# ver1_0.net
KiCad netlist of a schematic drawn in EAGLE
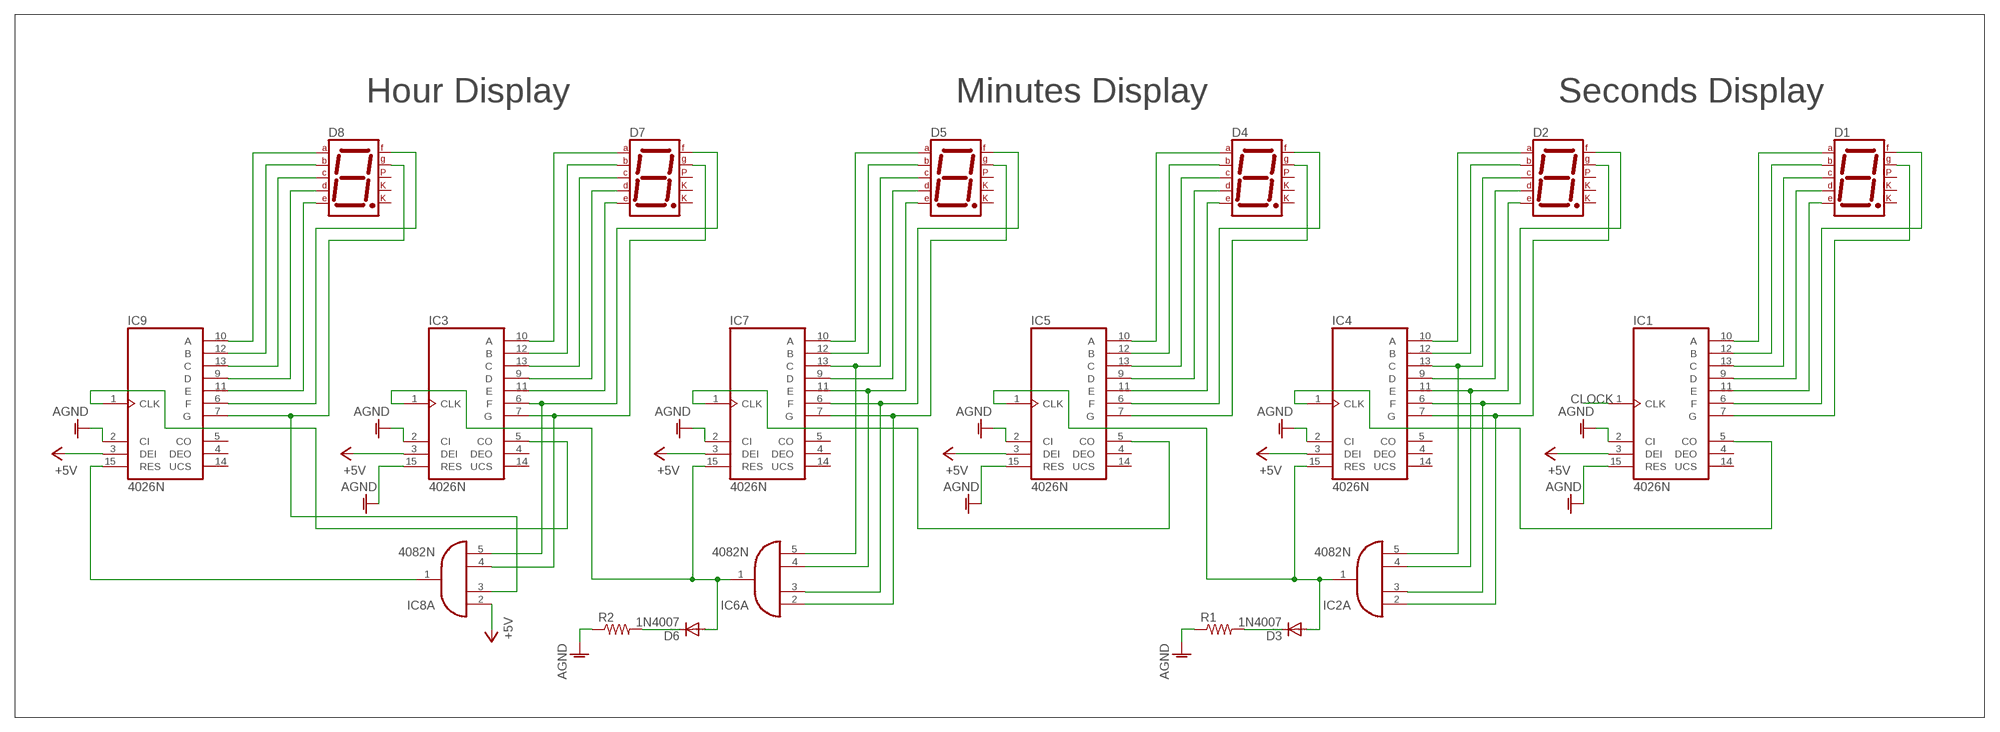
[diagram p0: schematic, sheet 1]

(export (version "E")
  (design (tool "Eeschema 10.0.6"))
  (components
    (comp (ref "D1")
      (value "7SEG-CK")
      (footprint "eagle-import:7SEG-13")
      (libsource (lib "eagle-import") (part "7SEG-CK"))
    )
    (comp (ref "D2")
      (value "7SEG-CK")
      (footprint "eagle-import:7SEG-13")
      (libsource (lib "eagle-import") (part "7SEG-CK"))
    )
    (comp (ref "D3")
      (value "1N4007")
      (footprint "eagle-import:DO41-10")
      (libsource (lib "eagle-import") (part "1N4004"))
    )
    (comp (ref "D4")
      (value "7SEG-CK")
      (footprint "eagle-import:7SEG-13")
      (libsource (lib "eagle-import") (part "7SEG-CK"))
    )
    (comp (ref "D5")
      (value "7SEG-CK")
      (footprint "eagle-import:7SEG-13")
      (libsource (lib "eagle-import") (part "7SEG-CK"))
    )
    (comp (ref "D6")
      (value "1N4007")
      (footprint "eagle-import:DO41-10")
      (libsource (lib "eagle-import") (part "1N4004"))
    )
    (comp (ref "D7")
      (value "7SEG-CK")
      (footprint "eagle-import:7SEG-13")
      (libsource (lib "eagle-import") (part "7SEG-CK"))
    )
    (comp (ref "D8")
      (value "7SEG-CK")
      (footprint "eagle-import:7SEG-13")
      (libsource (lib "eagle-import") (part "7SEG-CK"))
    )
    (comp (ref "IC1")
      (value "4026N")
      (footprint "eagle-import:DIL16")
      (libsource (lib "eagle-import") (part "4026N"))
    )
    (comp (ref "IC2")
      (value "4082N")
      (footprint "eagle-import:DIL14")
      (libsource (lib "eagle-import") (part "4082N"))
    )
    (comp (ref "IC3")
      (value "4026N")
      (footprint "eagle-import:DIL16")
      (libsource (lib "eagle-import") (part "4026N"))
    )
    (comp (ref "IC4")
      (value "4026N")
      (footprint "eagle-import:DIL16")
      (libsource (lib "eagle-import") (part "4026N"))
    )
    (comp (ref "IC5")
      (value "4026N")
      (footprint "eagle-import:DIL16")
      (libsource (lib "eagle-import") (part "4026N"))
    )
    (comp (ref "IC6")
      (value "4082N")
      (footprint "eagle-import:DIL14")
      (libsource (lib "eagle-import") (part "4082N"))
    )
    (comp (ref "IC7")
      (value "4026N")
      (footprint "eagle-import:DIL16")
      (libsource (lib "eagle-import") (part "4026N"))
    )
    (comp (ref "IC8")
      (value "4082N")
      (footprint "eagle-import:DIL14")
      (libsource (lib "eagle-import") (part "4082N"))
    )
    (comp (ref "IC9")
      (value "4026N")
      (footprint "eagle-import:DIL16")
      (libsource (lib "eagle-import") (part "4026N"))
    )
    (comp (ref "R1")
      (value "R-US_0204/2V")
      (footprint "eagle-import:0204V")
      (libsource (lib "eagle-import") (part "R-US_0204/2V"))
    )
    (comp (ref "R2")
      (value "R-US_0204/2V")
      (footprint "eagle-import:0204V")
      (libsource (lib "eagle-import") (part "R-US_0204/2V"))
    )
  )
  (nets
    (net (code "1") (name "+5V") (class "Default")
      (node (ref "IC1") (pin "3") (pinfunction "DEI_3") (pintype "input"))
      (node (ref "IC3") (pin "3") (pinfunction "DEI_3") (pintype "input"))
      (node (ref "IC4") (pin "3") (pinfunction "DEI_3") (pintype "input"))
      (node (ref "IC5") (pin "3") (pinfunction "DEI_3") (pintype "input"))
      (node (ref "IC7") (pin "3") (pinfunction "DEI_3") (pintype "input"))
      (node (ref "IC8") (pin "2") (pinfunction "I0_2") (pintype "input"))
      (node (ref "IC9") (pin "3") (pinfunction "DEI_3") (pintype "input"))
    )
    (net (code "2") (name "/CLOCK") (class "Default")
      (node (ref "IC1") (pin "1") (pinfunction "CLK_1") (pintype "input"))
    )
    (net (code "3") (name "AGND") (class "Default")
      (node (ref "IC1") (pin "15") (pinfunction "RES_15") (pintype "input"))
      (node (ref "IC1") (pin "2") (pinfunction "CI_2") (pintype "input"))
      (node (ref "IC3") (pin "15") (pinfunction "RES_15") (pintype "input"))
      (node (ref "IC3") (pin "2") (pinfunction "CI_2") (pintype "input"))
      (node (ref "IC4") (pin "2") (pinfunction "CI_2") (pintype "input"))
      (node (ref "IC5") (pin "15") (pinfunction "RES_15") (pintype "input"))
      (node (ref "IC5") (pin "2") (pinfunction "CI_2") (pintype "input"))
      (node (ref "IC7") (pin "2") (pinfunction "CI_2") (pintype "input"))
      (node (ref "IC9") (pin "2") (pinfunction "CI_2") (pintype "input"))
      (node (ref "R1") (pin "1") (pinfunction "1_1") (pintype "passive"))
      (node (ref "R2") (pin "1") (pinfunction "1_1") (pintype "passive"))
    )
    (net (code "4") (name "Net-(D1-A)") (class "Default")
      (node (ref "D1") (pin "7") (pinfunction "A_7") (pintype "passive"))
      (node (ref "IC1") (pin "10") (pinfunction "A_10") (pintype "output"))
    )
    (net (code "5") (name "Net-(D1-B)") (class "Default")
      (node (ref "D1") (pin "6") (pinfunction "B_6") (pintype "passive"))
      (node (ref "IC1") (pin "12") (pinfunction "B_12") (pintype "output"))
    )
    (net (code "6") (name "Net-(D1-C)") (class "Default")
      (node (ref "D1") (pin "4") (pinfunction "C_4") (pintype "passive"))
      (node (ref "IC1") (pin "13") (pinfunction "C_13") (pintype "output"))
    )
    (net (code "7") (name "Net-(D1-D)") (class "Default")
      (node (ref "D1") (pin "2") (pinfunction "D_2") (pintype "passive"))
      (node (ref "IC1") (pin "9") (pinfunction "D_9") (pintype "output"))
    )
    (net (code "8") (name "Net-(D1-E)") (class "Default")
      (node (ref "D1") (pin "1") (pinfunction "E_1") (pintype "passive"))
      (node (ref "IC1") (pin "11") (pinfunction "E_11") (pintype "output"))
    )
    (net (code "9") (name "Net-(D1-F)") (class "Default")
      (node (ref "D1") (pin "9") (pinfunction "F_9") (pintype "passive"))
      (node (ref "IC1") (pin "6") (pinfunction "F_6") (pintype "output"))
    )
    (net (code "10") (name "Net-(D1-G)") (class "Default")
      (node (ref "D1") (pin "10") (pinfunction "G_10") (pintype "passive"))
      (node (ref "IC1") (pin "7") (pinfunction "G_7") (pintype "output"))
    )
    (net (code "11") (name "Net-(D2-A)") (class "Default")
      (node (ref "D2") (pin "7") (pinfunction "A_7") (pintype "passive"))
      (node (ref "IC4") (pin "10") (pinfunction "A_10") (pintype "output"))
    )
    (net (code "12") (name "Net-(D2-B)") (class "Default")
      (node (ref "D2") (pin "6") (pinfunction "B_6") (pintype "passive"))
      (node (ref "IC4") (pin "12") (pinfunction "B_12") (pintype "output"))
    )
    (net (code "13") (name "Net-(D2-C)") (class "Default")
      (node (ref "D2") (pin "4") (pinfunction "C_4") (pintype "passive"))
      (node (ref "IC2") (pin "5") (pinfunction "I3_5") (pintype "input"))
      (node (ref "IC4") (pin "13") (pinfunction "C_13") (pintype "output"))
    )
    (net (code "14") (name "Net-(D2-D)") (class "Default")
      (node (ref "D2") (pin "2") (pinfunction "D_2") (pintype "passive"))
      (node (ref "IC4") (pin "9") (pinfunction "D_9") (pintype "output"))
    )
    (net (code "15") (name "Net-(D2-E)") (class "Default")
      (node (ref "D2") (pin "1") (pinfunction "E_1") (pintype "passive"))
      (node (ref "IC2") (pin "4") (pinfunction "I2_4") (pintype "input"))
      (node (ref "IC4") (pin "11") (pinfunction "E_11") (pintype "output"))
    )
    (net (code "16") (name "Net-(D2-F)") (class "Default")
      (node (ref "D2") (pin "9") (pinfunction "F_9") (pintype "passive"))
      (node (ref "IC2") (pin "3") (pinfunction "I1_3") (pintype "input"))
      (node (ref "IC4") (pin "6") (pinfunction "F_6") (pintype "output"))
    )
    (net (code "17") (name "Net-(D2-G)") (class "Default")
      (node (ref "D2") (pin "10") (pinfunction "G_10") (pintype "passive"))
      (node (ref "IC2") (pin "2") (pinfunction "I0_2") (pintype "input"))
      (node (ref "IC4") (pin "7") (pinfunction "G_7") (pintype "output"))
    )
    (net (code "18") (name "Net-(D3-PadC)") (class "Default")
      (node (ref "D3") (pin "C") (pinfunction "C_C") (pintype "passive"))
      (node (ref "R1") (pin "2") (pinfunction "2_2") (pintype "passive"))
    )
    (net (code "19") (name "Net-(D4-A)") (class "Default")
      (node (ref "D4") (pin "7") (pinfunction "A_7") (pintype "passive"))
      (node (ref "IC5") (pin "10") (pinfunction "A_10") (pintype "output"))
    )
    (net (code "20") (name "Net-(D4-B)") (class "Default")
      (node (ref "D4") (pin "6") (pinfunction "B_6") (pintype "passive"))
      (node (ref "IC5") (pin "12") (pinfunction "B_12") (pintype "output"))
    )
    (net (code "21") (name "Net-(D4-C)") (class "Default")
      (node (ref "D4") (pin "4") (pinfunction "C_4") (pintype "passive"))
      (node (ref "IC5") (pin "13") (pinfunction "C_13") (pintype "output"))
    )
    (net (code "22") (name "Net-(D4-D)") (class "Default")
      (node (ref "D4") (pin "2") (pinfunction "D_2") (pintype "passive"))
      (node (ref "IC5") (pin "9") (pinfunction "D_9") (pintype "output"))
    )
    (net (code "23") (name "Net-(D4-E)") (class "Default")
      (node (ref "D4") (pin "1") (pinfunction "E_1") (pintype "passive"))
      (node (ref "IC5") (pin "11") (pinfunction "E_11") (pintype "output"))
    )
    (net (code "24") (name "Net-(D4-F)") (class "Default")
      (node (ref "D4") (pin "9") (pinfunction "F_9") (pintype "passive"))
      (node (ref "IC5") (pin "6") (pinfunction "F_6") (pintype "output"))
    )
    (net (code "25") (name "Net-(D4-G)") (class "Default")
      (node (ref "D4") (pin "10") (pinfunction "G_10") (pintype "passive"))
      (node (ref "IC5") (pin "7") (pinfunction "G_7") (pintype "output"))
    )
    (net (code "26") (name "Net-(D5-A)") (class "Default")
      (node (ref "D5") (pin "7") (pinfunction "A_7") (pintype "passive"))
      (node (ref "IC7") (pin "10") (pinfunction "A_10") (pintype "output"))
    )
    (net (code "27") (name "Net-(D5-B)") (class "Default")
      (node (ref "D5") (pin "6") (pinfunction "B_6") (pintype "passive"))
      (node (ref "IC7") (pin "12") (pinfunction "B_12") (pintype "output"))
    )
    (net (code "28") (name "Net-(D5-C)") (class "Default")
      (node (ref "D5") (pin "4") (pinfunction "C_4") (pintype "passive"))
      (node (ref "IC6") (pin "5") (pinfunction "I3_5") (pintype "input"))
      (node (ref "IC7") (pin "13") (pinfunction "C_13") (pintype "output"))
    )
    (net (code "29") (name "Net-(D5-D)") (class "Default")
      (node (ref "D5") (pin "2") (pinfunction "D_2") (pintype "passive"))
      (node (ref "IC7") (pin "9") (pinfunction "D_9") (pintype "output"))
    )
    (net (code "30") (name "Net-(D5-E)") (class "Default")
      (node (ref "D5") (pin "1") (pinfunction "E_1") (pintype "passive"))
      (node (ref "IC6") (pin "4") (pinfunction "I2_4") (pintype "input"))
      (node (ref "IC7") (pin "11") (pinfunction "E_11") (pintype "output"))
    )
    (net (code "31") (name "Net-(D5-F)") (class "Default")
      (node (ref "D5") (pin "9") (pinfunction "F_9") (pintype "passive"))
      (node (ref "IC6") (pin "3") (pinfunction "I1_3") (pintype "input"))
      (node (ref "IC7") (pin "6") (pinfunction "F_6") (pintype "output"))
    )
    (net (code "32") (name "Net-(D5-G)") (class "Default")
      (node (ref "D5") (pin "10") (pinfunction "G_10") (pintype "passive"))
      (node (ref "IC6") (pin "2") (pinfunction "I0_2") (pintype "input"))
      (node (ref "IC7") (pin "7") (pinfunction "G_7") (pintype "output"))
    )
    (net (code "33") (name "Net-(D6-PadC)") (class "Default")
      (node (ref "D6") (pin "C") (pinfunction "C_C") (pintype "passive"))
      (node (ref "R2") (pin "2") (pinfunction "2_2") (pintype "passive"))
    )
    (net (code "34") (name "Net-(D7-A)") (class "Default")
      (node (ref "D7") (pin "7") (pinfunction "A_7") (pintype "passive"))
      (node (ref "IC3") (pin "10") (pinfunction "A_10") (pintype "output"))
    )
    (net (code "35") (name "Net-(D7-B)") (class "Default")
      (node (ref "D7") (pin "6") (pinfunction "B_6") (pintype "passive"))
      (node (ref "IC3") (pin "12") (pinfunction "B_12") (pintype "output"))
    )
    (net (code "36") (name "Net-(D7-C)") (class "Default")
      (node (ref "D7") (pin "4") (pinfunction "C_4") (pintype "passive"))
      (node (ref "IC3") (pin "13") (pinfunction "C_13") (pintype "output"))
    )
    (net (code "37") (name "Net-(D7-D)") (class "Default")
      (node (ref "D7") (pin "2") (pinfunction "D_2") (pintype "passive"))
      (node (ref "IC3") (pin "9") (pinfunction "D_9") (pintype "output"))
    )
    (net (code "38") (name "Net-(D7-E)") (class "Default")
      (node (ref "D7") (pin "1") (pinfunction "E_1") (pintype "passive"))
      (node (ref "IC3") (pin "11") (pinfunction "E_11") (pintype "output"))
    )
    (net (code "39") (name "Net-(D7-F)") (class "Default")
      (node (ref "D7") (pin "10") (pinfunction "G_10") (pintype "passive"))
      (node (ref "D7") (pin "9") (pinfunction "F_9") (pintype "passive"))
      (node (ref "IC3") (pin "6") (pinfunction "F_6") (pintype "output"))
      (node (ref "IC3") (pin "7") (pinfunction "G_7") (pintype "output"))
      (node (ref "IC8") (pin "4") (pinfunction "I2_4") (pintype "input"))
      (node (ref "IC8") (pin "5") (pinfunction "I3_5") (pintype "input"))
    )
    (net (code "40") (name "Net-(D8-A)") (class "Default")
      (node (ref "D8") (pin "7") (pinfunction "A_7") (pintype "passive"))
      (node (ref "IC9") (pin "10") (pinfunction "A_10") (pintype "output"))
    )
    (net (code "41") (name "Net-(D8-B)") (class "Default")
      (node (ref "D8") (pin "6") (pinfunction "B_6") (pintype "passive"))
      (node (ref "IC9") (pin "12") (pinfunction "B_12") (pintype "output"))
    )
    (net (code "42") (name "Net-(D8-C)") (class "Default")
      (node (ref "D8") (pin "4") (pinfunction "C_4") (pintype "passive"))
      (node (ref "IC9") (pin "13") (pinfunction "C_13") (pintype "output"))
    )
    (net (code "43") (name "Net-(D8-D)") (class "Default")
      (node (ref "D8") (pin "2") (pinfunction "D_2") (pintype "passive"))
      (node (ref "IC9") (pin "9") (pinfunction "D_9") (pintype "output"))
    )
    (net (code "44") (name "Net-(D8-E)") (class "Default")
      (node (ref "D8") (pin "1") (pinfunction "E_1") (pintype "passive"))
      (node (ref "IC9") (pin "11") (pinfunction "E_11") (pintype "output"))
    )
    (net (code "45") (name "Net-(D8-F)") (class "Default")
      (node (ref "D8") (pin "9") (pinfunction "F_9") (pintype "passive"))
      (node (ref "IC9") (pin "6") (pinfunction "F_6") (pintype "output"))
    )
    (net (code "46") (name "Net-(D8-G)") (class "Default")
      (node (ref "D8") (pin "10") (pinfunction "G_10") (pintype "passive"))
      (node (ref "IC8") (pin "3") (pinfunction "I1_3") (pintype "input"))
      (node (ref "IC9") (pin "7") (pinfunction "G_7") (pintype "output"))
    )
    (net (code "47") (name "Net-(IC1A-CO)") (class "Default")
      (node (ref "IC1") (pin "5") (pinfunction "CO_5") (pintype "output"))
      (node (ref "IC4") (pin "1") (pinfunction "CLK_1") (pintype "input"))
    )
    (net (code "48") (name "Net-(IC2A-O)") (class "Default")
      (node (ref "D3") (pin "A") (pinfunction "A_A") (pintype "passive"))
      (node (ref "IC2") (pin "1") (pinfunction "O_1") (pintype "output"))
      (node (ref "IC4") (pin "15") (pinfunction "RES_15") (pintype "input"))
      (node (ref "IC5") (pin "1") (pinfunction "CLK_1") (pintype "input"))
    )
    (net (code "49") (name "Net-(IC3A-CLK)") (class "Default")
      (node (ref "D6") (pin "A") (pinfunction "A_A") (pintype "passive"))
      (node (ref "IC3") (pin "1") (pinfunction "CLK_1") (pintype "input"))
      (node (ref "IC6") (pin "1") (pinfunction "O_1") (pintype "output"))
      (node (ref "IC7") (pin "15") (pinfunction "RES_15") (pintype "input"))
    )
    (net (code "50") (name "Net-(IC3A-CO)") (class "Default")
      (node (ref "IC3") (pin "5") (pinfunction "CO_5") (pintype "output"))
      (node (ref "IC9") (pin "1") (pinfunction "CLK_1") (pintype "input"))
    )
    (net (code "51") (name "Net-(IC5A-CO)") (class "Default")
      (node (ref "IC5") (pin "5") (pinfunction "CO_5") (pintype "output"))
      (node (ref "IC7") (pin "1") (pinfunction "CLK_1") (pintype "input"))
    )
    (net (code "52") (name "Net-(IC8A-O)") (class "Default")
      (node (ref "IC8") (pin "1") (pinfunction "O_1") (pintype "output"))
      (node (ref "IC9") (pin "15") (pinfunction "RES_15") (pintype "input"))
    )
    (net (code "53") (name "unconnected-(D1-CK1-Pad3)") (class "Default")
      (node (ref "D1") (pin "3") (pinfunction "CK1_3") (pintype "passive"))
    )
    (net (code "54") (name "unconnected-(D1-CK2-Pad8)") (class "Default")
      (node (ref "D1") (pin "8") (pinfunction "CK2_8") (pintype "passive"))
    )
    (net (code "55") (name "unconnected-(D1-DP-Pad5)") (class "Default")
      (node (ref "D1") (pin "5") (pinfunction "DP_5") (pintype "passive"))
    )
    (net (code "56") (name "unconnected-(D2-CK1-Pad3)") (class "Default")
      (node (ref "D2") (pin "3") (pinfunction "CK1_3") (pintype "passive"))
    )
    (net (code "57") (name "unconnected-(D2-CK2-Pad8)") (class "Default")
      (node (ref "D2") (pin "8") (pinfunction "CK2_8") (pintype "passive"))
    )
    (net (code "58") (name "unconnected-(D2-DP-Pad5)") (class "Default")
      (node (ref "D2") (pin "5") (pinfunction "DP_5") (pintype "passive"))
    )
    (net (code "59") (name "unconnected-(D4-CK1-Pad3)") (class "Default")
      (node (ref "D4") (pin "3") (pinfunction "CK1_3") (pintype "passive"))
    )
    (net (code "60") (name "unconnected-(D4-CK2-Pad8)") (class "Default")
      (node (ref "D4") (pin "8") (pinfunction "CK2_8") (pintype "passive"))
    )
    (net (code "61") (name "unconnected-(D4-DP-Pad5)") (class "Default")
      (node (ref "D4") (pin "5") (pinfunction "DP_5") (pintype "passive"))
    )
    (net (code "62") (name "unconnected-(D5-CK1-Pad3)") (class "Default")
      (node (ref "D5") (pin "3") (pinfunction "CK1_3") (pintype "passive"))
    )
    (net (code "63") (name "unconnected-(D5-CK2-Pad8)") (class "Default")
      (node (ref "D5") (pin "8") (pinfunction "CK2_8") (pintype "passive"))
    )
    (net (code "64") (name "unconnected-(D5-DP-Pad5)") (class "Default")
      (node (ref "D5") (pin "5") (pinfunction "DP_5") (pintype "passive"))
    )
    (net (code "65") (name "unconnected-(D7-CK1-Pad3)") (class "Default")
      (node (ref "D7") (pin "3") (pinfunction "CK1_3") (pintype "passive"))
    )
    (net (code "66") (name "unconnected-(D7-CK2-Pad8)") (class "Default")
      (node (ref "D7") (pin "8") (pinfunction "CK2_8") (pintype "passive"))
    )
    (net (code "67") (name "unconnected-(D7-DP-Pad5)") (class "Default")
      (node (ref "D7") (pin "5") (pinfunction "DP_5") (pintype "passive"))
    )
    (net (code "68") (name "unconnected-(D8-CK1-Pad3)") (class "Default")
      (node (ref "D8") (pin "3") (pinfunction "CK1_3") (pintype "passive"))
    )
    (net (code "69") (name "unconnected-(D8-CK2-Pad8)") (class "Default")
      (node (ref "D8") (pin "8") (pinfunction "CK2_8") (pintype "passive"))
    )
    (net (code "70") (name "unconnected-(D8-DP-Pad5)") (class "Default")
      (node (ref "D8") (pin "5") (pinfunction "DP_5") (pintype "passive"))
    )
    (net (code "71") (name "unconnected-(IC1A-DEO-Pad4)") (class "Default")
      (node (ref "IC1") (pin "4") (pinfunction "DEO_4") (pintype "output"))
    )
    (net (code "72") (name "unconnected-(IC1A-UCS-Pad14)") (class "Default")
      (node (ref "IC1") (pin "14") (pinfunction "UCS_14") (pintype "output"))
    )
    (net (code "73") (name "unconnected-(IC3A-DEO-Pad4)") (class "Default")
      (node (ref "IC3") (pin "4") (pinfunction "DEO_4") (pintype "output"))
    )
    (net (code "74") (name "unconnected-(IC3A-UCS-Pad14)") (class "Default")
      (node (ref "IC3") (pin "14") (pinfunction "UCS_14") (pintype "output"))
    )
    (net (code "75") (name "unconnected-(IC4A-CO-Pad5)") (class "Default")
      (node (ref "IC4") (pin "5") (pinfunction "CO_5") (pintype "output"))
    )
    (net (code "76") (name "unconnected-(IC4A-DEO-Pad4)") (class "Default")
      (node (ref "IC4") (pin "4") (pinfunction "DEO_4") (pintype "output"))
    )
    (net (code "77") (name "unconnected-(IC4A-UCS-Pad14)") (class "Default")
      (node (ref "IC4") (pin "14") (pinfunction "UCS_14") (pintype "output"))
    )
    (net (code "78") (name "unconnected-(IC5A-DEO-Pad4)") (class "Default")
      (node (ref "IC5") (pin "4") (pinfunction "DEO_4") (pintype "output"))
    )
    (net (code "79") (name "unconnected-(IC5A-UCS-Pad14)") (class "Default")
      (node (ref "IC5") (pin "14") (pinfunction "UCS_14") (pintype "output"))
    )
    (net (code "80") (name "unconnected-(IC7A-CO-Pad5)") (class "Default")
      (node (ref "IC7") (pin "5") (pinfunction "CO_5") (pintype "output"))
    )
    (net (code "81") (name "unconnected-(IC7A-DEO-Pad4)") (class "Default")
      (node (ref "IC7") (pin "4") (pinfunction "DEO_4") (pintype "output"))
    )
    (net (code "82") (name "unconnected-(IC7A-UCS-Pad14)") (class "Default")
      (node (ref "IC7") (pin "14") (pinfunction "UCS_14") (pintype "output"))
    )
    (net (code "83") (name "unconnected-(IC9A-CO-Pad5)") (class "Default")
      (node (ref "IC9") (pin "5") (pinfunction "CO_5") (pintype "output"))
    )
    (net (code "84") (name "unconnected-(IC9A-DEO-Pad4)") (class "Default")
      (node (ref "IC9") (pin "4") (pinfunction "DEO_4") (pintype "output"))
    )
    (net (code "85") (name "unconnected-(IC9A-UCS-Pad14)") (class "Default")
      (node (ref "IC9") (pin "14") (pinfunction "UCS_14") (pintype "output"))
    )
  )
)
